# Schematic-_Shield.net
KiCad netlist of a schematic drawn in EasyEDA
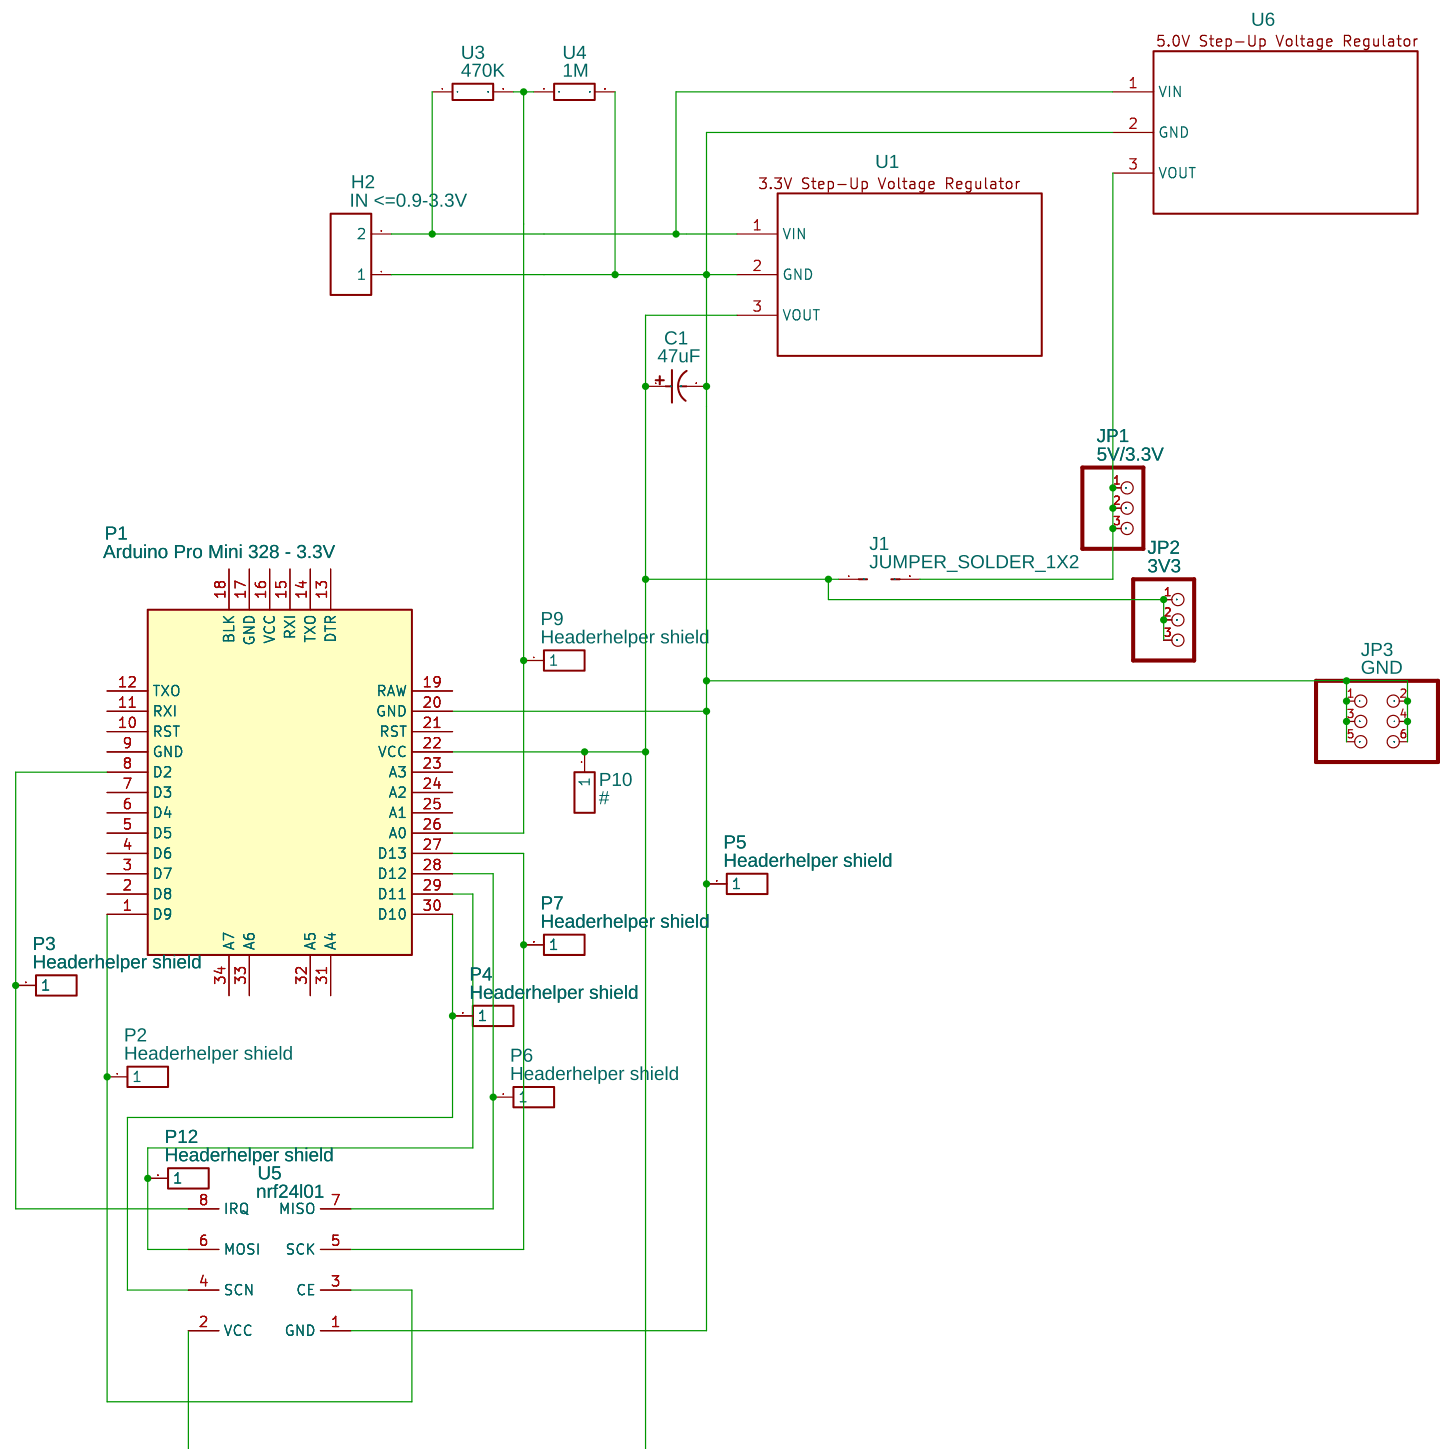
[diagram p0: schematic sheet]

(export (version "E")
  (design (tool "Eeschema 10.0.6"))
  (components
    (comp (ref "C1")
      (value "47uF")
      (fields (field (name "BOM_Manufacturer Part") "47UF16V") (field (name "BOM_Supplier Part") "C30224"))
      (libsource (lib "") (part "47UF16V"))
    )
    (comp (ref "H2")
      (value "IN <=0.9-3.3V")
      (fields (field (name "BOM_Manufacturer Part") "826629-2") (field (name "BOM_Supplier Part") "C86471"))
      (libsource (lib "") (part "Unknown_340_155"))
    )
    (comp (ref "J1") (value "JUMPER_SOLDER_1X2") (libsource (lib "") (part "Unknown_595_315")))
    (comp (ref "JP1") (value "5V/3.3V") (libsource (lib "") (part "Unknown_710_280")))
    (comp (ref "JP2") (value "3V3") (libsource (lib "") (part "Unknown_735_335")))
    (comp (ref "JP3") (value "GND") (libsource (lib "") (part "Unknown_840_385")))
    (comp (ref "P1") (value "Arduino Pro Mini 328 - 3.3V") (libsource (lib "") (part "Unknown_300_415")))
    (comp (ref "P2")
      (value "Headerhelper shield")
      (fields
        (field (name "BOM_Manufacturer Part") "Header-Male-2.54_1x1")
        (field (name "BOM_Supplier Part") "C81276")
      )
      (libsource (lib "") (part "Unknown_230_560"))
    )
    (comp (ref "P3")
      (value "Headerhelper shield")
      (fields
        (field (name "BOM_Manufacturer Part") "Header-Male-2.54_1x1")
        (field (name "BOM_Supplier Part") "C81276")
      )
      (libsource (lib "") (part "Unknown_185_515"))
    )
    (comp (ref "P4")
      (value "Headerhelper shield")
      (fields
        (field (name "BOM_Manufacturer Part") "Header-Male-2.54_1x1")
        (field (name "BOM_Supplier Part") "C81276")
      )
      (libsource (lib "") (part "Unknown_400_530"))
    )
    (comp (ref "P5")
      (value "Headerhelper shield")
      (fields
        (field (name "BOM_Manufacturer Part") "Header-Male-2.54_1x1")
        (field (name "BOM_Supplier Part") "C81276")
      )
      (libsource (lib "") (part "Unknown_525_465"))
    )
    (comp (ref "P6")
      (value "Headerhelper shield")
      (fields
        (field (name "BOM_Manufacturer Part") "Header-Male-2.54_1x1")
        (field (name "BOM_Supplier Part") "C81276")
      )
      (libsource (lib "") (part "Unknown_420_570"))
    )
    (comp (ref "P7")
      (value "Headerhelper shield")
      (fields
        (field (name "BOM_Manufacturer Part") "Header-Male-2.54_1x1")
        (field (name "BOM_Supplier Part") "C81276")
      )
      (libsource (lib "") (part "Unknown_435_495"))
    )
    (comp (ref "P9")
      (value "Headerhelper shield")
      (fields
        (field (name "BOM_Manufacturer Part") "Header-Male-2.54_1x1")
        (field (name "BOM_Supplier Part") "C81276")
      )
      (libsource (lib "") (part "Unknown_435_355"))
    )
    (comp (ref "P10")
      (value "#")
      (fields
        (field (name "BOM_Manufacturer Part") "Header-Male-2.54_1x1")
        (field (name "BOM_Supplier Part") "C81276")
      )
      (libsource (lib "") (part "Unknown_450_415"))
    )
    (comp (ref "P12")
      (value "Headerhelper shield")
      (fields
        (field (name "BOM_Manufacturer Part") "Header-Male-2.54_1x1")
        (field (name "BOM_Supplier Part") "C81276")
      )
      (libsource (lib "") (part "Unknown_250_610"))
    )
    (comp (ref "U1")
      (value "3.3V Step-Up Voltage Regulator NCP1402")
      (libsource (lib "") (part "Unknown_605_160"))
    )
    (comp (ref "U3")
      (value "470K")
      (fields
        (field (name "BOM_Manufacturer Part") "MOF2WS-470Ω±5% T")
        (field (name "BOM_Supplier Part") "C121655")
      )
      (libsource (lib "") (part "MOF2WS-470Ω±5% T"))
    )
    (comp (ref "U4")
      (value "1M")
      (fields
        (field (name "BOM_Manufacturer Part") "MOF2WS-470Ω±5% T")
        (field (name "BOM_Supplier Part") "C121655")
      )
      (libsource (lib "") (part "MOF2WS-470Ω±5% T"))
    )
    (comp (ref "U5")
      (value "nrf24l01")
      (fields (field (name "BOM_Manufacturer Part") "nrf2401l"))
      (libsource (lib "") (part "Unknown_305_655"))
    )
    (comp (ref "U6")
      (value "3.3V Step-Up Voltage Regulator NCP1402")
      (libsource (lib "") (part "Unknown_790_90"))
    )
  )
  (nets
    (net (code "1") (name "Net-(P1-A0)") (class "Default")
      (node (ref "P1") (pin "26") (pinfunction "A0_26") (pintype "unspecified"))
      (node (ref "P9") (pin "1") (pinfunction "1_1") (pintype "input"))
      (node (ref "U3") (pin "2") (pinfunction "2_2") (pintype "input"))
      (node (ref "U4") (pin "1") (pinfunction "1_1") (pintype "input"))
    )
    (net (code "2") (name "Net-(P1-D2)") (class "Default")
      (node (ref "P1") (pin "8") (pinfunction "D2_8") (pintype "unspecified"))
      (node (ref "P3") (pin "1") (pinfunction "1_1") (pintype "input"))
      (node (ref "U5") (pin "8") (pinfunction "IRQ_8") (pintype "unspecified"))
    )
    (net (code "3") (name "Net-(P1-D9)") (class "Default")
      (node (ref "P1") (pin "1") (pinfunction "D9_1") (pintype "unspecified"))
      (node (ref "P2") (pin "1") (pinfunction "1_1") (pintype "input"))
      (node (ref "U5") (pin "3") (pinfunction "CE_3") (pintype "unspecified"))
    )
    (net (code "4") (name "Net-(P1-D10)") (class "Default")
      (node (ref "P1") (pin "30") (pinfunction "D10_30") (pintype "unspecified"))
      (node (ref "P4") (pin "1") (pinfunction "1_1") (pintype "input"))
      (node (ref "U5") (pin "4") (pinfunction "SCN_4") (pintype "unspecified"))
    )
    (net (code "5") (name "Net-(P1-D11)") (class "Default")
      (node (ref "P1") (pin "29") (pinfunction "D11_29") (pintype "unspecified"))
      (node (ref "P12") (pin "1") (pinfunction "1_1") (pintype "input"))
      (node (ref "U5") (pin "6") (pinfunction "MOSI_6") (pintype "unspecified"))
    )
    (net (code "6") (name "Net-(P1-D12)") (class "Default")
      (node (ref "P1") (pin "28") (pinfunction "D12_28") (pintype "unspecified"))
      (node (ref "P6") (pin "1") (pinfunction "1_1") (pintype "input"))
      (node (ref "U5") (pin "7") (pinfunction "MISO_7") (pintype "unspecified"))
    )
    (net (code "7") (name "Net-(P1-D13)") (class "Default")
      (node (ref "P1") (pin "27") (pinfunction "D13_27") (pintype "unspecified"))
      (node (ref "P7") (pin "1") (pinfunction "1_1") (pintype "input"))
      (node (ref "U5") (pin "5") (pinfunction "SCK_5") (pintype "unspecified"))
    )
    (net (code "8") (name "Net-(U1-GND)") (class "Default")
      (node (ref "C1") (pin "2") (pinfunction "2_2") (pintype "input"))
      (node (ref "H2") (pin "1") (pinfunction "1_1") (pintype "unspecified"))
      (node (ref "JP3") (pin "1") (pinfunction "1_1") (pintype "unspecified"))
      (node (ref "JP3") (pin "2") (pinfunction "2_2") (pintype "unspecified"))
      (node (ref "JP3") (pin "3") (pinfunction "3_3") (pintype "unspecified"))
      (node (ref "JP3") (pin "4") (pinfunction "4_4") (pintype "unspecified"))
      (node (ref "JP3") (pin "5") (pinfunction "5_5") (pintype "unspecified"))
      (node (ref "JP3") (pin "6") (pinfunction "6_6") (pintype "unspecified"))
      (node (ref "P1") (pin "20") (pinfunction "GND_20") (pintype "unspecified"))
      (node (ref "P5") (pin "1") (pinfunction "1_1") (pintype "input"))
      (node (ref "U1") (pin "2") (pinfunction "GND_2") (pintype "unspecified"))
      (node (ref "U4") (pin "2") (pinfunction "2_2") (pintype "input"))
      (node (ref "U5") (pin "1") (pinfunction "GND_1") (pintype "unspecified"))
      (node (ref "U6") (pin "2") (pinfunction "GND_2") (pintype "unspecified"))
    )
    (net (code "9") (name "Net-(U1-VIN)") (class "Default")
      (node (ref "H2") (pin "2") (pinfunction "2_2") (pintype "unspecified"))
      (node (ref "U1") (pin "1") (pinfunction "VIN_1") (pintype "unspecified"))
      (node (ref "U3") (pin "1") (pinfunction "1_1") (pintype "input"))
      (node (ref "U6") (pin "1") (pinfunction "VIN_1") (pintype "unspecified"))
    )
    (net (code "10") (name "Net-(U1-VOUT)") (class "Default")
      (node (ref "C1") (pin "1") (pinfunction "1_1") (pintype "input"))
      (node (ref "J1") (pin "1") (pinfunction "1_1") (pintype "unspecified"))
      (node (ref "JP2") (pin "1") (pinfunction "1_1") (pintype "unspecified"))
      (node (ref "JP2") (pin "2") (pinfunction "2_2") (pintype "unspecified"))
      (node (ref "JP2") (pin "3") (pinfunction "3_3") (pintype "unspecified"))
      (node (ref "P1") (pin "22") (pinfunction "VCC_22") (pintype "unspecified"))
      (node (ref "P10") (pin "1") (pinfunction "1_1") (pintype "input"))
      (node (ref "U1") (pin "3") (pinfunction "VOUT_3") (pintype "unspecified"))
      (node (ref "U5") (pin "2") (pinfunction "VCC_2") (pintype "unspecified"))
    )
    (net (code "11") (name "Net-(U6-VOUT)") (class "Default")
      (node (ref "J1") (pin "2") (pinfunction "2_2") (pintype "unspecified"))
      (node (ref "JP1") (pin "1") (pinfunction "1_1") (pintype "unspecified"))
      (node (ref "JP1") (pin "2") (pinfunction "2_2") (pintype "unspecified"))
      (node (ref "JP1") (pin "3") (pinfunction "3_3") (pintype "unspecified"))
      (node (ref "U6") (pin "3") (pinfunction "VOUT_3") (pintype "unspecified"))
    )
    (net (code "12") (name "unconnected-(P1-A1-Pad25)") (class "Default")
      (node (ref "P1") (pin "25") (pinfunction "A1_25") (pintype "unspecified"))
    )
    (net (code "13") (name "unconnected-(P1-A2-Pad24)") (class "Default")
      (node (ref "P1") (pin "24") (pinfunction "A2_24") (pintype "unspecified"))
    )
    (net (code "14") (name "unconnected-(P1-A3-Pad23)") (class "Default")
      (node (ref "P1") (pin "23") (pinfunction "A3_23") (pintype "unspecified"))
    )
    (net (code "15") (name "unconnected-(P1-A4-Pad31)") (class "Default")
      (node (ref "P1") (pin "31") (pinfunction "A4_31") (pintype "unspecified"))
    )
    (net (code "16") (name "unconnected-(P1-A5-Pad32)") (class "Default")
      (node (ref "P1") (pin "32") (pinfunction "A5_32") (pintype "unspecified"))
    )
    (net (code "17") (name "unconnected-(P1-A6-Pad33)") (class "Default")
      (node (ref "P1") (pin "33") (pinfunction "A6_33") (pintype "unspecified"))
    )
    (net (code "18") (name "unconnected-(P1-A7-Pad34)") (class "Default")
      (node (ref "P1") (pin "34") (pinfunction "A7_34") (pintype "unspecified"))
    )
    (net (code "19") (name "unconnected-(P1-BLK-Pad18)") (class "Default")
      (node (ref "P1") (pin "18") (pinfunction "BLK_18") (pintype "unspecified"))
    )
    (net (code "20") (name "unconnected-(P1-D3-Pad7)") (class "Default")
      (node (ref "P1") (pin "7") (pinfunction "D3_7") (pintype "unspecified"))
    )
    (net (code "21") (name "unconnected-(P1-D4-Pad6)") (class "Default")
      (node (ref "P1") (pin "6") (pinfunction "D4_6") (pintype "unspecified"))
    )
    (net (code "22") (name "unconnected-(P1-D5-Pad5)") (class "Default")
      (node (ref "P1") (pin "5") (pinfunction "D5_5") (pintype "unspecified"))
    )
    (net (code "23") (name "unconnected-(P1-D6-Pad4)") (class "Default")
      (node (ref "P1") (pin "4") (pinfunction "D6_4") (pintype "unspecified"))
    )
    (net (code "24") (name "unconnected-(P1-D7-Pad3)") (class "Default")
      (node (ref "P1") (pin "3") (pinfunction "D7_3") (pintype "unspecified"))
    )
    (net (code "25") (name "unconnected-(P1-D8-Pad2)") (class "Default")
      (node (ref "P1") (pin "2") (pinfunction "D8_2") (pintype "unspecified"))
    )
    (net (code "26") (name "unconnected-(P1-DTR-Pad13)") (class "Default")
      (node (ref "P1") (pin "13") (pinfunction "DTR_13") (pintype "unspecified"))
    )
    (net (code "27") (name "unconnected-(P1-GND-Pad9)") (class "Default")
      (node (ref "P1") (pin "9") (pinfunction "GND_9") (pintype "unspecified"))
    )
    (net (code "28") (name "unconnected-(P1-GND-Pad17)") (class "Default")
      (node (ref "P1") (pin "17") (pinfunction "GND_17") (pintype "unspecified"))
    )
    (net (code "29") (name "unconnected-(P1-RAW-Pad19)") (class "Default")
      (node (ref "P1") (pin "19") (pinfunction "RAW_19") (pintype "unspecified"))
    )
    (net (code "30") (name "unconnected-(P1-RST-Pad10)") (class "Default")
      (node (ref "P1") (pin "10") (pinfunction "RST_10") (pintype "unspecified"))
    )
    (net (code "31") (name "unconnected-(P1-RST-Pad21)") (class "Default")
      (node (ref "P1") (pin "21") (pinfunction "RST_21") (pintype "unspecified"))
    )
    (net (code "32") (name "unconnected-(P1-RXI-Pad11)") (class "Default")
      (node (ref "P1") (pin "11") (pinfunction "RXI_11") (pintype "unspecified"))
    )
    (net (code "33") (name "unconnected-(P1-RXI-Pad15)") (class "Default")
      (node (ref "P1") (pin "15") (pinfunction "RXI_15") (pintype "unspecified"))
    )
    (net (code "34") (name "unconnected-(P1-TXO-Pad12)") (class "Default")
      (node (ref "P1") (pin "12") (pinfunction "TXO_12") (pintype "unspecified"))
    )
    (net (code "35") (name "unconnected-(P1-TXO-Pad14)") (class "Default")
      (node (ref "P1") (pin "14") (pinfunction "TXO_14") (pintype "unspecified"))
    )
    (net (code "36") (name "unconnected-(P1-VCC-Pad16)") (class "Default")
      (node (ref "P1") (pin "16") (pinfunction "VCC_16") (pintype "unspecified"))
    )
  )
)
